# dw-shield-V1_1.net
KiCad netlist of a schematic drawn in EAGLE
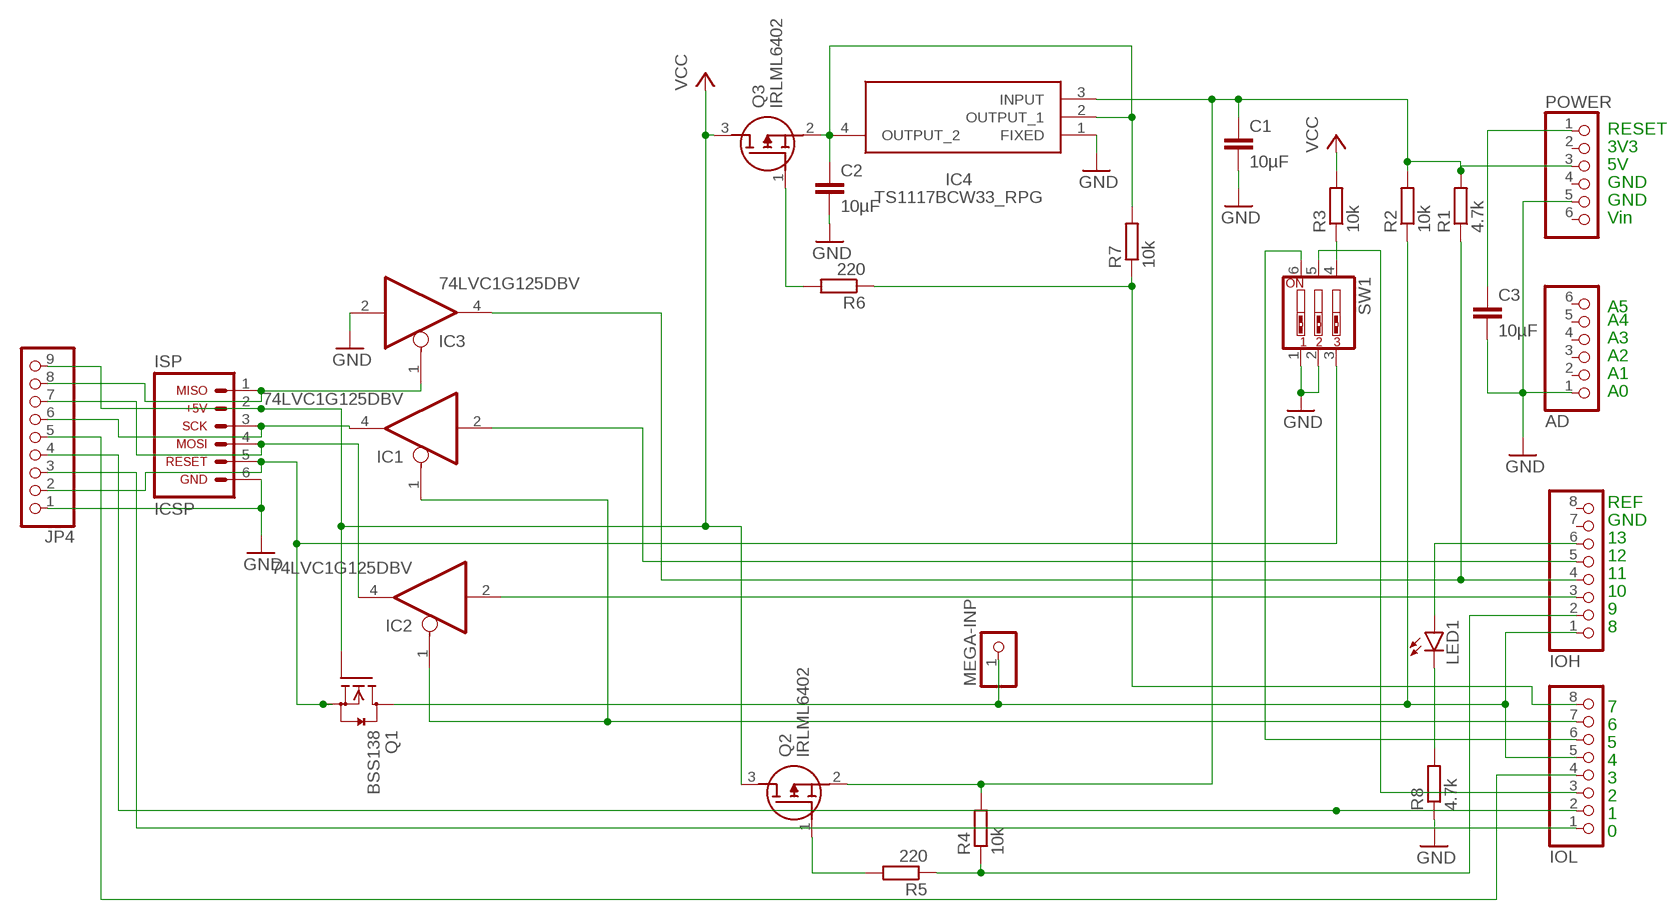
[diagram p0: schematic, sheet 1]

(export (version "E")
  (design (tool "Eeschema 10.0.6"))
  (components
    (comp (ref "AD")
      (value "PINHD-1X6")
      (footprint "eagle-import:1X06")
      (libsource (lib "eagle-import") (part "PINHD-1X6"))
    )
    (comp (ref "C1")
      (value "10µF")
      (footprint "eagle-import:C1206")
      (libsource (lib "eagle-import") (part "C-EUC1206"))
    )
    (comp (ref "C2")
      (value "10µF")
      (footprint "eagle-import:C1206")
      (libsource (lib "eagle-import") (part "C-EUC1206"))
    )
    (comp (ref "C3")
      (value "10µF")
      (footprint "eagle-import:C1206")
      (libsource (lib "eagle-import") (part "C-EUC1206"))
    )
    (comp (ref "IC1")
      (value "74LVC1G125DBV")
      (footprint "eagle-import:SOT23-5")
      (libsource (lib "eagle-import") (part "741G125DBVLVC"))
    )
    (comp (ref "IC2")
      (value "74LVC1G125DBV")
      (footprint "eagle-import:SOT23-5")
      (libsource (lib "eagle-import") (part "741G125DBVLVC"))
    )
    (comp (ref "IC3")
      (value "74LVC1G125DBV")
      (footprint "eagle-import:SOT23-5")
      (libsource (lib "eagle-import") (part "741G125DBVLVC"))
    )
    (comp (ref "IC4")
      (value "TS1117BCW33_RPG")
      (footprint "eagle-import:SOT230P700X190-4N")
      (fields
        (field (name "ARROW_PART_NUMBER") "TS1117BCW33 RPG")
        (field (name "MOUSER_PART_NUMBER") "821-TS1117BCW33RPG")
      )
      (libsource (lib "eagle-import") (part "TS1117BCW33_RPG"))
    )
    (comp (ref "IOH")
      (value "PINHD-1X8")
      (footprint "eagle-import:1X08")
      (libsource (lib "eagle-import") (part "PINHD-1X8"))
    )
    (comp (ref "IOL")
      (value "PINHD-1X8")
      (footprint "eagle-import:1X08")
      (libsource (lib "eagle-import") (part "PINHD-1X8"))
    )
    (comp (ref "ISP")
      (value "ARDUINO_CONN-ICSP")
      (footprint "eagle-import:CONN-2X03")
      (libsource (lib "eagle-import") (part "ARDUINO_CONN-ICSP"))
    )
    (comp (ref "JP4")
      (value "PINHD-1X9")
      (footprint "eagle-import:1X09")
      (libsource (lib "eagle-import") (part "PINHD-1X9"))
    )
    (comp (ref "LED1")
      (value "LEDCHIPLED_1206")
      (footprint "eagle-import:CHIPLED_1206")
      (libsource (lib "eagle-import") (part "LEDCHIPLED_1206"))
    )
    (comp (ref "MEGA-INP")
      (value "PINHD-1X1")
      (footprint "eagle-import:1X01")
      (libsource (lib "eagle-import") (part "PINHD-1X1"))
    )
    (comp (ref "POWER")
      (value "PINHD-1X6")
      (footprint "eagle-import:1X06")
      (libsource (lib "eagle-import") (part "PINHD-1X6"))
    )
    (comp (ref "Q1")
      (value "BSS138")
      (footprint "eagle-import:SOT23")
      (libsource (lib "eagle-import") (part "BSS138"))
    )
    (comp (ref "Q2")
      (value "IRLML6402")
      (footprint "eagle-import:SOT95P237X112-3N")
      (libsource (lib "eagle-import") (part "IRLML6402"))
    )
    (comp (ref "Q3")
      (value "IRLML6402")
      (footprint "eagle-import:SOT95P237X112-3N")
      (libsource (lib "eagle-import") (part "IRLML6402"))
    )
    (comp (ref "R1")
      (value "4.7k")
      (footprint "eagle-import:R1206")
      (libsource (lib "eagle-import") (part "R-EU_R1206"))
    )
    (comp (ref "R2")
      (value "10k")
      (footprint "eagle-import:R1206")
      (libsource (lib "eagle-import") (part "R-EU_R1206"))
    )
    (comp (ref "R3")
      (value "10k")
      (footprint "eagle-import:R1206")
      (libsource (lib "eagle-import") (part "R-EU_R1206"))
    )
    (comp (ref "R4")
      (value "10k")
      (footprint "eagle-import:R1206")
      (libsource (lib "eagle-import") (part "R-EU_R1206"))
    )
    (comp (ref "R5")
      (value "220")
      (footprint "eagle-import:R1206")
      (libsource (lib "eagle-import") (part "R-EU_R1206"))
    )
    (comp (ref "R6")
      (value "220")
      (footprint "eagle-import:R1206")
      (libsource (lib "eagle-import") (part "R-EU_R1206"))
    )
    (comp (ref "R7")
      (value "10k")
      (footprint "eagle-import:R1206")
      (libsource (lib "eagle-import") (part "R-EU_R1206"))
    )
    (comp (ref "R8")
      (value "4.7k")
      (footprint "eagle-import:R1206")
      (libsource (lib "eagle-import") (part "R-EU_R1206"))
    )
    (comp (ref "SW1")
      (value "SW_DIP-3")
      (footprint "eagle-import:EDG-03")
      (libsource (lib "eagle-import") (part "SW_DIP-3"))
    )
  )
  (nets
    (net (code "1") (name "GND") (class "Default")
      (node (ref "AD") (pin "1") (pinfunction "1_1") (pintype "passive"))
      (node (ref "C1") (pin "2") (pinfunction "2_2") (pintype "passive"))
      (node (ref "C2") (pin "2") (pinfunction "2_2") (pintype "passive"))
      (node (ref "C3") (pin "2") (pinfunction "2_2") (pintype "passive"))
      (node (ref "IC3") (pin "2") (pinfunction "I_2") (pintype "input"))
      (node (ref "IC4") (pin "1") (pinfunction "FIXED_1") (pintype "bidirectional"))
      (node (ref "ISP") (pin "6") (pinfunction "6_6") (pintype "passive"))
      (node (ref "JP4") (pin "1") (pinfunction "1_1") (pintype "passive"))
      (node (ref "POWER") (pin "5") (pinfunction "5_5") (pintype "passive"))
      (node (ref "R8") (pin "1") (pinfunction "1_1") (pintype "passive"))
      (node (ref "SW1") (pin "1") (pinfunction "1_1") (pintype "passive"))
      (node (ref "SW1") (pin "2") (pinfunction "2_2") (pintype "passive"))
    )
    (net (code "2") (name "Net-(C3-Pad1)") (class "Default")
      (node (ref "C3") (pin "1") (pinfunction "1_1") (pintype "passive"))
      (node (ref "POWER") (pin "1") (pinfunction "1_1") (pintype "passive"))
    )
    (net (code "3") (name "Net-(IC1A-I)") (class "Default")
      (node (ref "IC1") (pin "2") (pinfunction "I_2") (pintype "input"))
      (node (ref "IOH") (pin "5") (pinfunction "5_5") (pintype "passive"))
    )
    (net (code "4") (name "Net-(IC1A-O)") (class "Default")
      (node (ref "IC1") (pin "4") (pinfunction "O_4") (pintype "tri_state"))
      (node (ref "ISP") (pin "3") (pinfunction "3_3") (pintype "passive"))
      (node (ref "JP4") (pin "6") (pinfunction "6_6") (pintype "passive"))
    )
    (net (code "5") (name "Net-(IC1A-OE)") (class "Default")
      (node (ref "IC1") (pin "1") (pinfunction "OE_1") (pintype "input"))
      (node (ref "IC2") (pin "1") (pinfunction "OE_1") (pintype "input"))
      (node (ref "IOL") (pin "7") (pinfunction "7_7") (pintype "passive"))
    )
    (net (code "6") (name "Net-(IC2A-I)") (class "Default")
      (node (ref "IC2") (pin "2") (pinfunction "I_2") (pintype "input"))
      (node (ref "IOH") (pin "3") (pinfunction "3_3") (pintype "passive"))
    )
    (net (code "7") (name "Net-(IC2A-O)") (class "Default")
      (node (ref "IC2") (pin "4") (pinfunction "O_4") (pintype "tri_state"))
      (node (ref "ISP") (pin "4") (pinfunction "4_4") (pintype "passive"))
      (node (ref "JP4") (pin "7") (pinfunction "7_7") (pintype "passive"))
    )
    (net (code "8") (name "Net-(IC3A-O)") (class "Default")
      (node (ref "IC3") (pin "4") (pinfunction "O_4") (pintype "tri_state"))
      (node (ref "IOH") (pin "4") (pinfunction "4_4") (pintype "passive"))
      (node (ref "R1") (pin "1") (pinfunction "1_1") (pintype "passive"))
    )
    (net (code "9") (name "Net-(IC3A-OE)") (class "Default")
      (node (ref "IC3") (pin "1") (pinfunction "OE_1") (pintype "input"))
      (node (ref "ISP") (pin "1") (pinfunction "1_1") (pintype "passive"))
      (node (ref "JP4") (pin "8") (pinfunction "8_8") (pintype "passive"))
    )
    (net (code "10") (name "Net-(IC4-INPUT)") (class "Default")
      (node (ref "C1") (pin "1") (pinfunction "1_1") (pintype "passive"))
      (node (ref "IC4") (pin "3") (pinfunction "INPUT_3") (pintype "bidirectional"))
      (node (ref "POWER") (pin "3") (pinfunction "3_3") (pintype "passive"))
      (node (ref "Q2") (pin "2") (pinfunction "S_2") (pintype "bidirectional"))
      (node (ref "R1") (pin "2") (pinfunction "2_2") (pintype "passive"))
      (node (ref "R2") (pin "2") (pinfunction "2_2") (pintype "passive"))
      (node (ref "R4") (pin "2") (pinfunction "2_2") (pintype "passive"))
    )
    (net (code "11") (name "Net-(IC4-OUTPUT_1)") (class "Default")
      (node (ref "C2") (pin "1") (pinfunction "1_1") (pintype "passive"))
      (node (ref "IC4") (pin "2") (pinfunction "OUTPUT_1_2") (pintype "bidirectional"))
      (node (ref "IC4") (pin "4") (pinfunction "OUTPUT_2_4") (pintype "bidirectional"))
      (node (ref "Q3") (pin "2") (pinfunction "S_2") (pintype "bidirectional"))
      (node (ref "R7") (pin "2") (pinfunction "2_2") (pintype "passive"))
    )
    (net (code "12") (name "Net-(IOH-Pad2)") (class "Default")
      (node (ref "IOH") (pin "2") (pinfunction "2_2") (pintype "passive"))
      (node (ref "R4") (pin "1") (pinfunction "1_1") (pintype "passive"))
      (node (ref "R5") (pin "1") (pinfunction "1_1") (pintype "passive"))
    )
    (net (code "13") (name "Net-(IOH-Pad6)") (class "Default")
      (node (ref "IOH") (pin "6") (pinfunction "6_6") (pintype "passive"))
      (node (ref "LED1") (pin "A") (pinfunction "A_A") (pintype "passive"))
    )
    (net (code "14") (name "Net-(IOL-Pad1)") (class "Default")
      (node (ref "IOL") (pin "1") (pinfunction "1_1") (pintype "passive"))
      (node (ref "JP4") (pin "3") (pinfunction "3_3") (pintype "passive"))
    )
    (net (code "15") (name "Net-(IOL-Pad2)") (class "Default")
      (node (ref "IOL") (pin "2") (pinfunction "2_2") (pintype "passive"))
      (node (ref "JP4") (pin "4") (pinfunction "4_4") (pintype "passive"))
    )
    (net (code "16") (name "Net-(IOL-Pad3)") (class "Default")
      (node (ref "IOL") (pin "3") (pinfunction "3_3") (pintype "passive"))
      (node (ref "SW1") (pin "5") (pinfunction "5_5") (pintype "passive"))
    )
    (net (code "17") (name "Net-(IOL-Pad4)") (class "Default")
      (node (ref "IOL") (pin "4") (pinfunction "4_4") (pintype "passive"))
      (node (ref "JP4") (pin "5") (pinfunction "5_5") (pintype "passive"))
    )
    (net (code "18") (name "Net-(IOL-Pad6)") (class "Default")
      (node (ref "IOL") (pin "6") (pinfunction "6_6") (pintype "passive"))
      (node (ref "SW1") (pin "6") (pinfunction "6_6") (pintype "passive"))
    )
    (net (code "19") (name "Net-(IOL-Pad8)") (class "Default")
      (node (ref "IOL") (pin "8") (pinfunction "8_8") (pintype "passive"))
      (node (ref "R6") (pin "1") (pinfunction "1_1") (pintype "passive"))
      (node (ref "R7") (pin "1") (pinfunction "1_1") (pintype "passive"))
    )
    (net (code "20") (name "Net-(LED1-PadC)") (class "Default")
      (node (ref "LED1") (pin "C") (pinfunction "C_C") (pintype "passive"))
      (node (ref "R8") (pin "2") (pinfunction "2_2") (pintype "passive"))
    )
    (net (code "21") (name "Net-(Q1-D)") (class "Default")
      (node (ref "IOH") (pin "1") (pinfunction "1_1") (pintype "passive"))
      (node (ref "IOL") (pin "5") (pinfunction "5_5") (pintype "passive"))
      (node (ref "MEGA-INP") (pin "1") (pinfunction "1_1") (pintype "passive"))
      (node (ref "Q1") (pin "3") (pinfunction "D_3") (pintype "passive"))
      (node (ref "R2") (pin "1") (pinfunction "1_1") (pintype "passive"))
    )
    (net (code "22") (name "Net-(Q1-S)") (class "Default")
      (node (ref "ISP") (pin "5") (pinfunction "5_5") (pintype "passive"))
      (node (ref "JP4") (pin "2") (pinfunction "2_2") (pintype "passive"))
      (node (ref "Q1") (pin "2") (pinfunction "S_2") (pintype "passive"))
      (node (ref "SW1") (pin "3") (pinfunction "3_3") (pintype "passive"))
    )
    (net (code "23") (name "Net-(Q2-G)") (class "Default")
      (node (ref "Q2") (pin "1") (pinfunction "G_1") (pintype "bidirectional"))
      (node (ref "R5") (pin "2") (pinfunction "2_2") (pintype "passive"))
    )
    (net (code "24") (name "Net-(Q3-G)") (class "Default")
      (node (ref "Q3") (pin "1") (pinfunction "G_1") (pintype "bidirectional"))
      (node (ref "R6") (pin "2") (pinfunction "2_2") (pintype "passive"))
    )
    (net (code "25") (name "Net-(R3-Pad1)") (class "Default")
      (node (ref "R3") (pin "1") (pinfunction "1_1") (pintype "passive"))
      (node (ref "SW1") (pin "4") (pinfunction "4_4") (pintype "passive"))
    )
    (net (code "26") (name "VCC") (class "Default")
      (node (ref "ISP") (pin "2") (pinfunction "2_2") (pintype "passive"))
      (node (ref "JP4") (pin "9") (pinfunction "9_9") (pintype "passive"))
      (node (ref "Q1") (pin "1") (pinfunction "G_1") (pintype "passive"))
      (node (ref "Q2") (pin "3") (pinfunction "D_3") (pintype "bidirectional"))
      (node (ref "Q3") (pin "3") (pinfunction "D_3") (pintype "bidirectional"))
      (node (ref "R3") (pin "2") (pinfunction "2_2") (pintype "passive"))
    )
    (net (code "27") (name "unconnected-(AD-Pad2)") (class "Default")
      (node (ref "AD") (pin "2") (pinfunction "2_2") (pintype "passive"))
    )
    (net (code "28") (name "unconnected-(AD-Pad3)") (class "Default")
      (node (ref "AD") (pin "3") (pinfunction "3_3") (pintype "passive"))
    )
    (net (code "29") (name "unconnected-(AD-Pad4)") (class "Default")
      (node (ref "AD") (pin "4") (pinfunction "4_4") (pintype "passive"))
    )
    (net (code "30") (name "unconnected-(AD-Pad5)") (class "Default")
      (node (ref "AD") (pin "5") (pinfunction "5_5") (pintype "passive"))
    )
    (net (code "31") (name "unconnected-(AD-Pad6)") (class "Default")
      (node (ref "AD") (pin "6") (pinfunction "6_6") (pintype "passive"))
    )
    (net (code "32") (name "unconnected-(IOH-Pad7)") (class "Default")
      (node (ref "IOH") (pin "7") (pinfunction "7_7") (pintype "passive"))
    )
    (net (code "33") (name "unconnected-(IOH-Pad8)") (class "Default")
      (node (ref "IOH") (pin "8") (pinfunction "8_8") (pintype "passive"))
    )
    (net (code "34") (name "unconnected-(POWER-Pad2)") (class "Default")
      (node (ref "POWER") (pin "2") (pinfunction "2_2") (pintype "passive"))
    )
    (net (code "35") (name "unconnected-(POWER-Pad4)") (class "Default")
      (node (ref "POWER") (pin "4") (pinfunction "4_4") (pintype "passive"))
    )
    (net (code "36") (name "unconnected-(POWER-Pad6)") (class "Default")
      (node (ref "POWER") (pin "6") (pinfunction "6_6") (pintype "passive"))
    )
  )
)
